# synapse.net
KiCad netlist of a schematic drawn in EAGLE
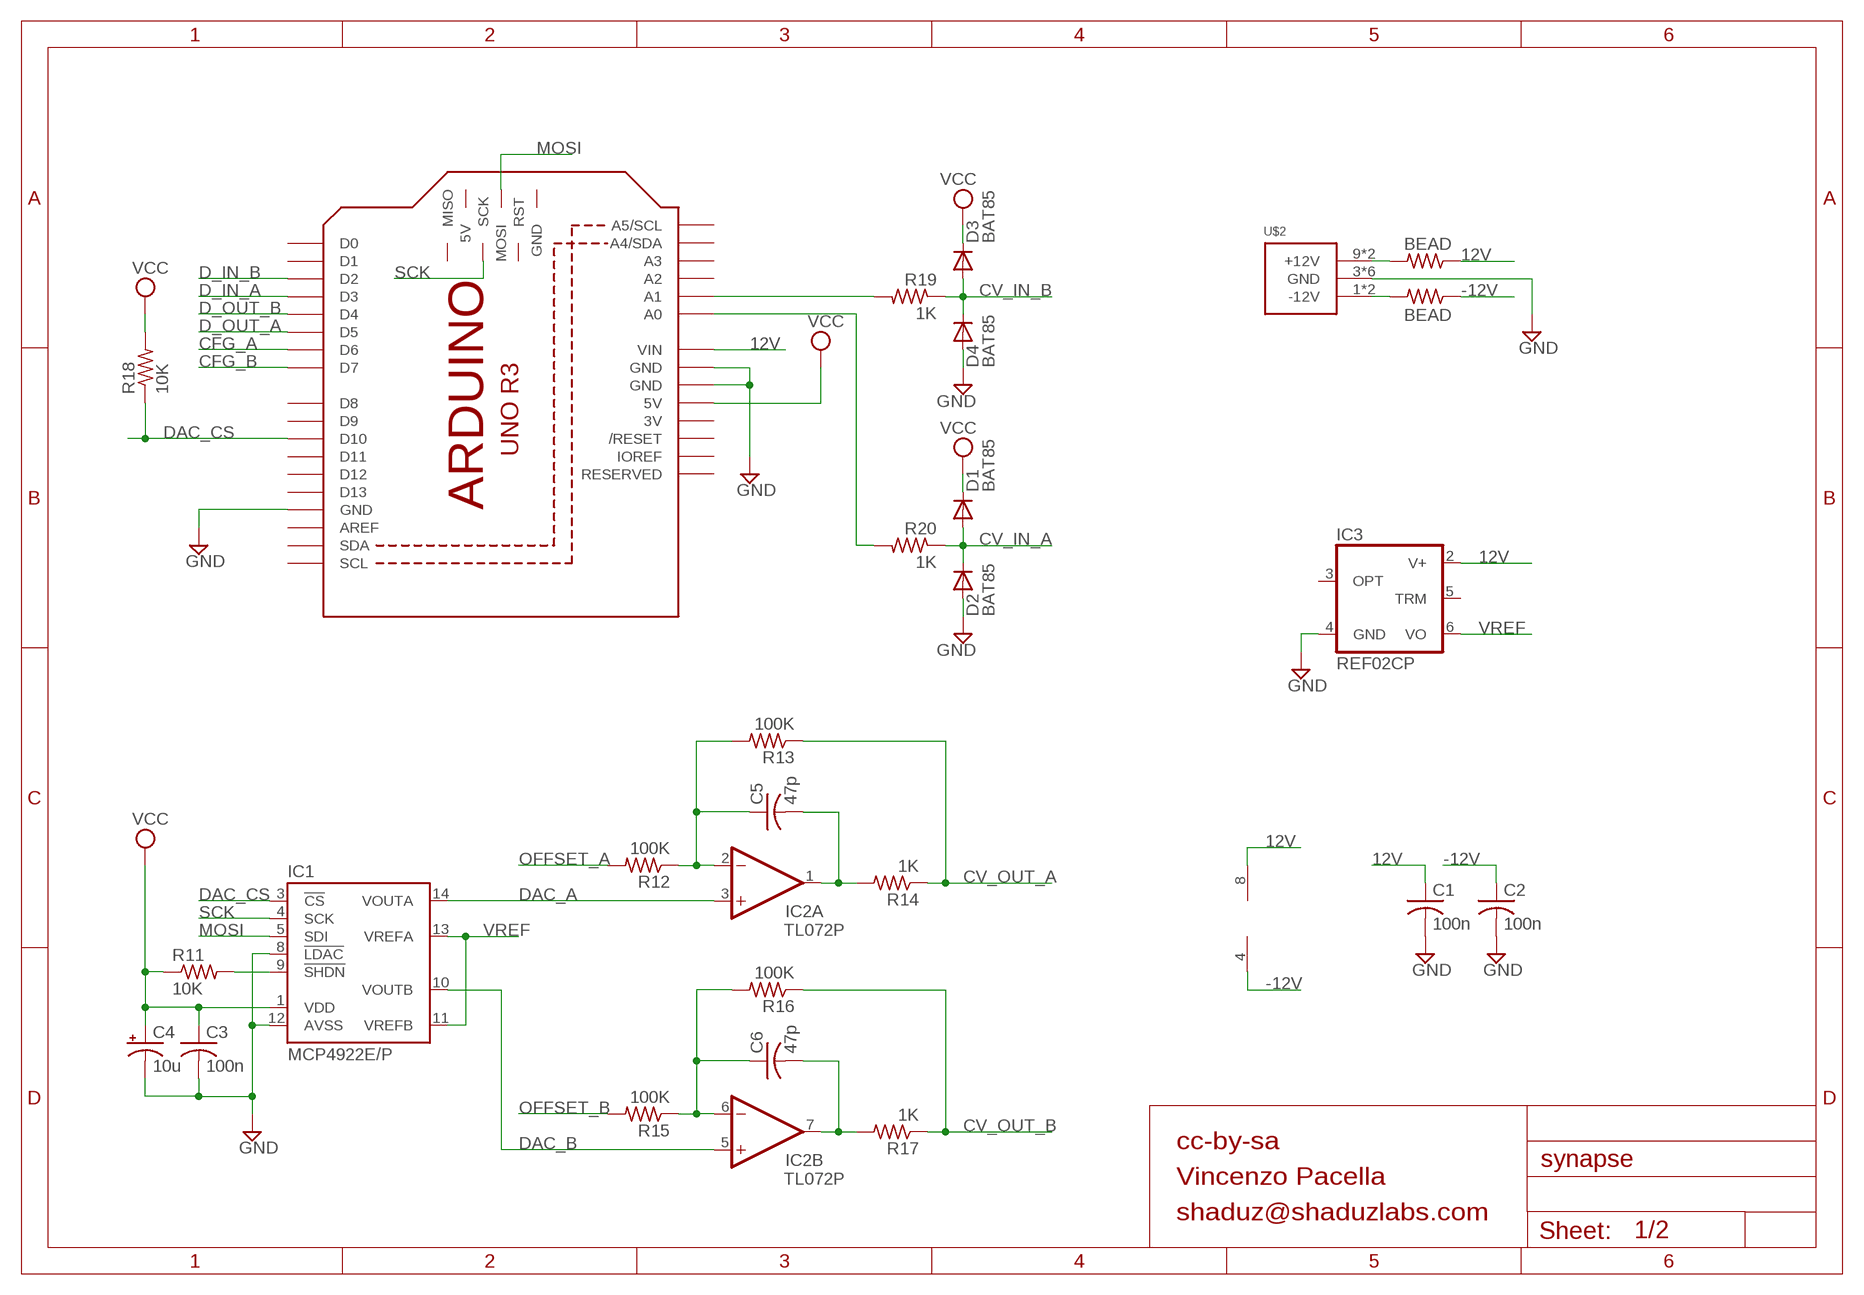
[diagram p0: schematic, sheet 1]
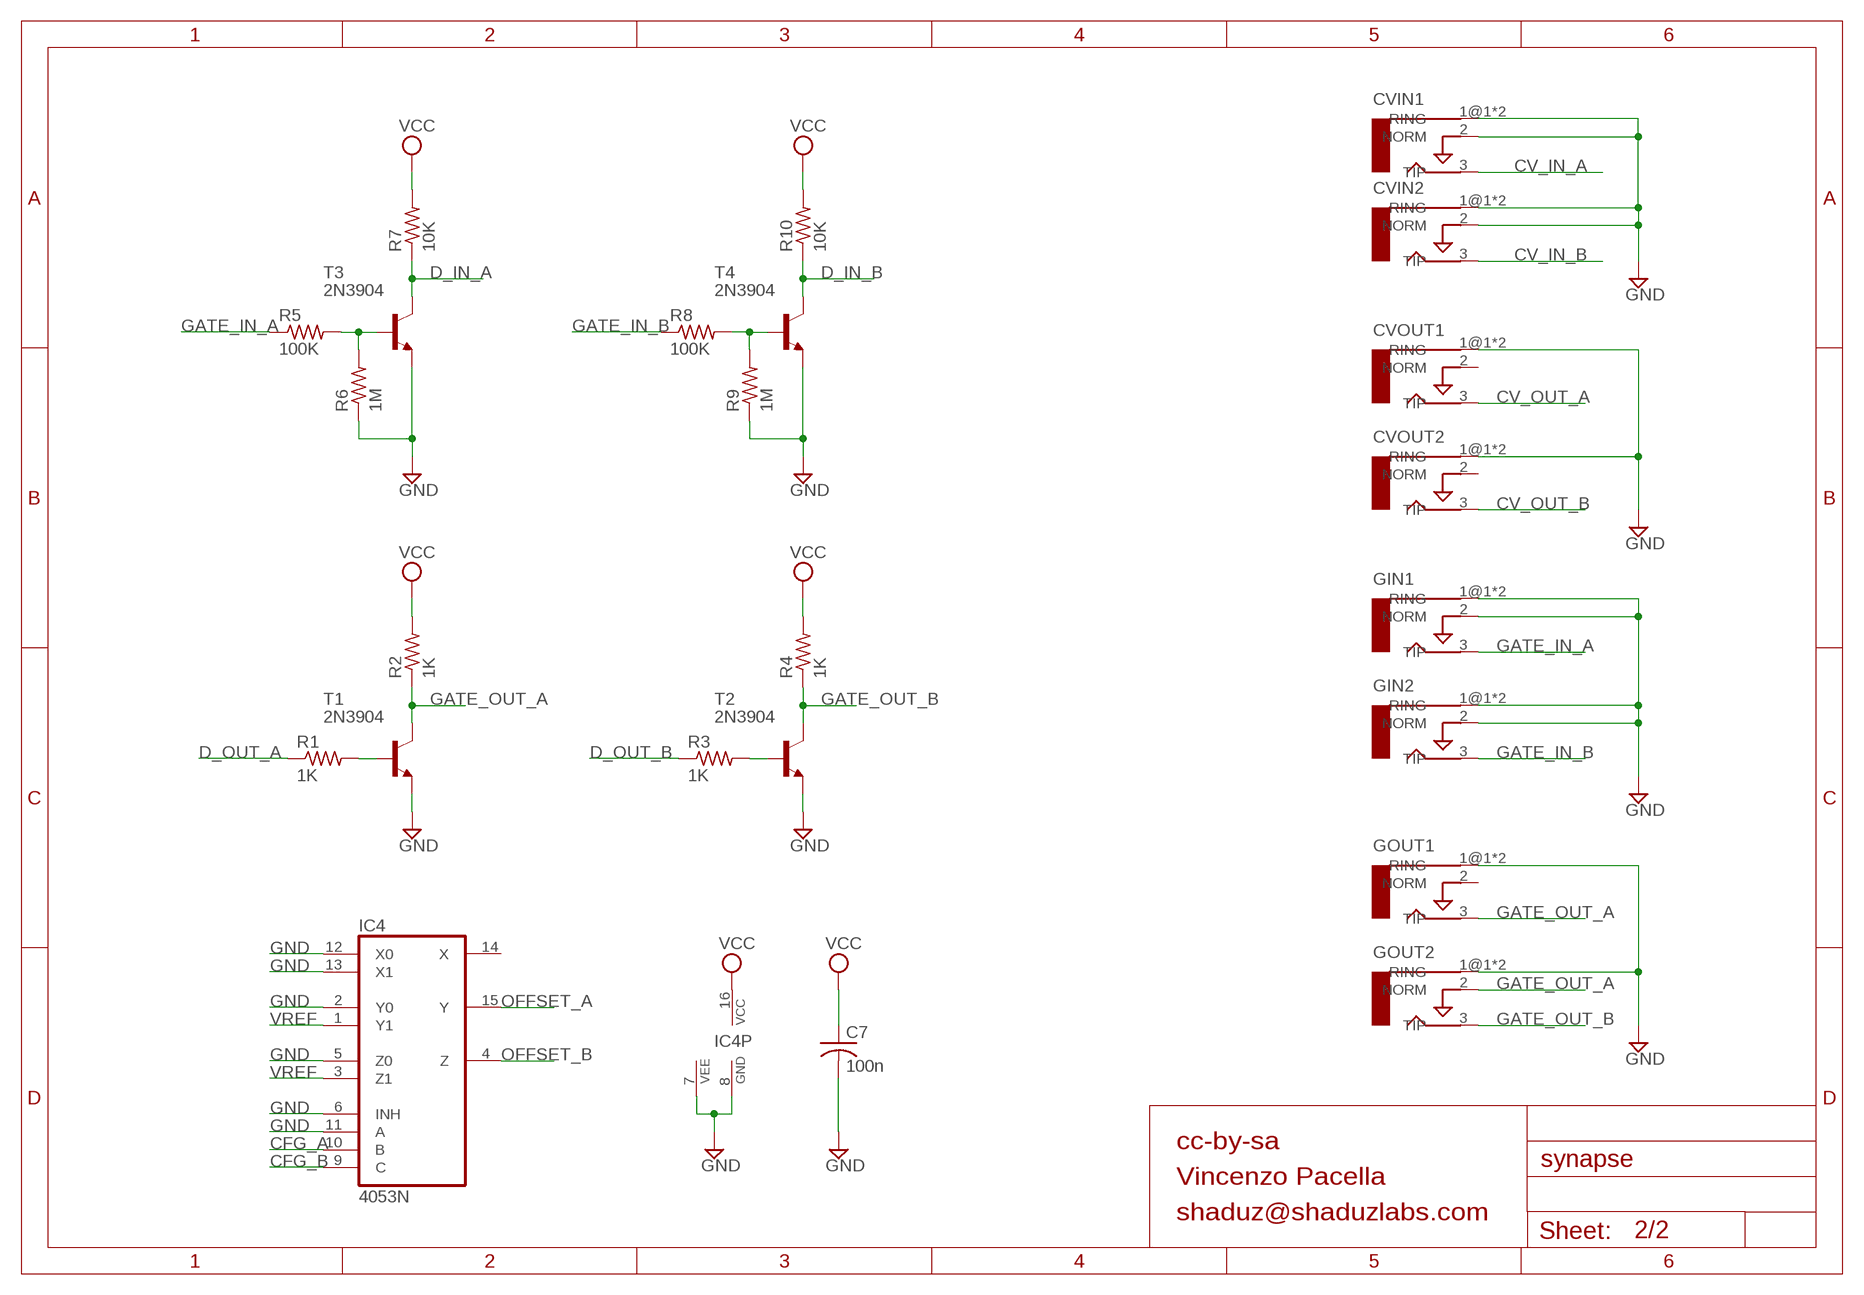
[diagram p1: schematic, sheet 2]

(export (version "E")
  (design (tool "Eeschema 10.0.6"))
  (components
    (comp (ref "C1")
      (value "100n")
      (footprint "eagle-import:C025-025X050")
      (libsource (lib "eagle-import") (part "C-US025-025X050"))
    )
    (comp (ref "C2")
      (value "100n")
      (footprint "eagle-import:C025-025X050")
      (libsource (lib "eagle-import") (part "C-US025-025X050"))
    )
    (comp (ref "C3")
      (value "100n")
      (footprint "eagle-import:C025-025X050")
      (libsource (lib "eagle-import") (part "C-US025-025X050"))
    )
    (comp (ref "C4")
      (value "10u")
      (footprint "eagle-import:E2-5")
      (libsource (lib "eagle-import") (part "CPOL-USE2-5"))
    )
    (comp (ref "C5")
      (value "47p")
      (footprint "eagle-import:C025-025X050")
      (libsource (lib "eagle-import") (part "C-US025-025X050"))
    )
    (comp (ref "C6")
      (value "47p")
      (footprint "eagle-import:C025-025X050")
      (libsource (lib "eagle-import") (part "C-US025-025X050"))
    )
    (comp (ref "D1")
      (value "BAT85")
      (footprint "eagle-import:D-5")
      (libsource (lib "eagle-import") (part "DIODE-D-5"))
    )
    (comp (ref "D2")
      (value "BAT85")
      (footprint "eagle-import:D-5")
      (libsource (lib "eagle-import") (part "DIODE-D-5"))
    )
    (comp (ref "D3")
      (value "BAT85")
      (footprint "eagle-import:D-5")
      (libsource (lib "eagle-import") (part "DIODE-D-5"))
    )
    (comp (ref "D4")
      (value "BAT85")
      (footprint "eagle-import:D-5")
      (libsource (lib "eagle-import") (part "DIODE-D-5"))
    )
    (comp (ref "IC1")
      (value "MCP4922E/P")
      (footprint "eagle-import:DIL14")
      (libsource (lib "eagle-import") (part "MCP4922E/P"))
    )
    (comp (ref "IC2")
      (value "TL072P")
      (footprint "eagle-import:DIL08")
      (libsource (lib "eagle-import") (part "TL072P"))
    )
    (comp (ref "IC3")
      (value "REF02CP")
      (footprint "eagle-import:DIL08")
      (libsource (lib "eagle-import") (part "REF02Z"))
    )
    (comp (ref "M1")
      (value "ARDUINO_R3_ICSP")
      (footprint "eagle-import:ARDUINOR3_ICSP")
      (libsource (lib "eagle-import") (part "ARDUINO_R3_ICSP"))
    )
    (comp (ref "R11")
      (value "10K")
      (footprint "eagle-import:0204_7")
      (libsource (lib "eagle-import") (part "R-US_0204/7"))
    )
    (comp (ref "R12")
      (value "100K")
      (footprint "eagle-import:0204_7")
      (libsource (lib "eagle-import") (part "R-US_0204/7"))
    )
    (comp (ref "R13")
      (value "100K")
      (footprint "eagle-import:0204_7")
      (libsource (lib "eagle-import") (part "R-US_0204/7"))
    )
    (comp (ref "R14")
      (value "1K")
      (footprint "eagle-import:0204_7")
      (libsource (lib "eagle-import") (part "R-US_0204/7"))
    )
    (comp (ref "R15")
      (value "100K")
      (footprint "eagle-import:0204_7")
      (libsource (lib "eagle-import") (part "R-US_0204/7"))
    )
    (comp (ref "R16")
      (value "100K")
      (footprint "eagle-import:0204_7")
      (libsource (lib "eagle-import") (part "R-US_0204/7"))
    )
    (comp (ref "R17")
      (value "1K")
      (footprint "eagle-import:0204_7")
      (libsource (lib "eagle-import") (part "R-US_0204/7"))
    )
    (comp (ref "R18")
      (value "10K")
      (footprint "eagle-import:0204_7")
      (libsource (lib "eagle-import") (part "R-US_0204/7"))
    )
    (comp (ref "R19")
      (value "1K")
      (footprint "eagle-import:0204_7")
      (libsource (lib "eagle-import") (part "R-US_0204/7"))
    )
    (comp (ref "R20")
      (value "1K")
      (footprint "eagle-import:0204_7")
      (libsource (lib "eagle-import") (part "R-US_0204/7"))
    )
    (comp (ref "R21")
      (value "BEAD")
      (footprint "eagle-import:0204_7")
      (libsource (lib "eagle-import") (part "R-US_0204/7"))
    )
    (comp (ref "R24")
      (value "BEAD")
      (footprint "eagle-import:0204_7")
      (libsource (lib "eagle-import") (part "R-US_0204/7"))
    )
    (comp (ref "U$2")
      (value "POWER_SIMPLE10")
      (footprint "eagle-import:POWER_10")
      (libsource (lib "eagle-import") (part "POWER_SIMPLE10"))
    )
    (comp (ref "C7")
      (value "100n")
      (footprint "eagle-import:C025-025X050")
      (libsource (lib "eagle-import") (part "C-US025-025X050"))
    )
    (comp (ref "CVIN1")
      (value "AUDIO-JACKERTHENVAR")
      (footprint "eagle-import:ERTHENVAR-JACK")
      (libsource (lib "eagle-import") (part "AUDIO-JACKERTHENVAR"))
    )
    (comp (ref "CVIN2")
      (value "AUDIO-JACKERTHENVAR")
      (footprint "eagle-import:ERTHENVAR-JACK")
      (libsource (lib "eagle-import") (part "AUDIO-JACKERTHENVAR"))
    )
    (comp (ref "CVOUT1")
      (value "AUDIO-JACKERTHENVAR")
      (footprint "eagle-import:ERTHENVAR-JACK")
      (libsource (lib "eagle-import") (part "AUDIO-JACKERTHENVAR"))
    )
    (comp (ref "CVOUT2")
      (value "AUDIO-JACKERTHENVAR")
      (footprint "eagle-import:ERTHENVAR-JACK")
      (libsource (lib "eagle-import") (part "AUDIO-JACKERTHENVAR"))
    )
    (comp (ref "GIN1")
      (value "AUDIO-JACKERTHENVAR")
      (footprint "eagle-import:ERTHENVAR-JACK")
      (libsource (lib "eagle-import") (part "AUDIO-JACKERTHENVAR"))
    )
    (comp (ref "GIN2")
      (value "AUDIO-JACKERTHENVAR")
      (footprint "eagle-import:ERTHENVAR-JACK")
      (libsource (lib "eagle-import") (part "AUDIO-JACKERTHENVAR"))
    )
    (comp (ref "GOUT1")
      (value "AUDIO-JACKERTHENVAR")
      (footprint "eagle-import:ERTHENVAR-JACK")
      (libsource (lib "eagle-import") (part "AUDIO-JACKERTHENVAR"))
    )
    (comp (ref "GOUT2")
      (value "AUDIO-JACKERTHENVAR")
      (footprint "eagle-import:ERTHENVAR-JACK")
      (libsource (lib "eagle-import") (part "AUDIO-JACKERTHENVAR"))
    )
    (comp (ref "IC4")
      (value "4053N")
      (footprint "eagle-import:DIL16")
      (libsource (lib "eagle-import") (part "4053N"))
    )
    (comp (ref "R1")
      (value "1K")
      (footprint "eagle-import:0204_7")
      (libsource (lib "eagle-import") (part "R-US_0204/7"))
    )
    (comp (ref "R2")
      (value "1K")
      (footprint "eagle-import:0204_7")
      (libsource (lib "eagle-import") (part "R-US_0204/7"))
    )
    (comp (ref "R3")
      (value "1K")
      (footprint "eagle-import:0204_7")
      (libsource (lib "eagle-import") (part "R-US_0204/7"))
    )
    (comp (ref "R4")
      (value "1K")
      (footprint "eagle-import:0204_7")
      (libsource (lib "eagle-import") (part "R-US_0204/7"))
    )
    (comp (ref "R5")
      (value "100K")
      (footprint "eagle-import:0204_7")
      (libsource (lib "eagle-import") (part "R-US_0204/7"))
    )
    (comp (ref "R6")
      (value "1M")
      (footprint "eagle-import:0204_7")
      (libsource (lib "eagle-import") (part "R-US_0204/7"))
    )
    (comp (ref "R7")
      (value "10K")
      (footprint "eagle-import:0204_7")
      (libsource (lib "eagle-import") (part "R-US_0204/7"))
    )
    (comp (ref "R8")
      (value "100K")
      (footprint "eagle-import:0204_7")
      (libsource (lib "eagle-import") (part "R-US_0204/7"))
    )
    (comp (ref "R9")
      (value "1M")
      (footprint "eagle-import:0204_7")
      (libsource (lib "eagle-import") (part "R-US_0204/7"))
    )
    (comp (ref "R10")
      (value "10K")
      (footprint "eagle-import:0204_7")
      (libsource (lib "eagle-import") (part "R-US_0204/7"))
    )
    (comp (ref "T1")
      (value "2N3904")
      (footprint "eagle-import:TO92-EBC")
      (libsource (lib "eagle-import") (part "-NPN-TO92-EBC2N3904"))
    )
    (comp (ref "T2")
      (value "2N3904")
      (footprint "eagle-import:TO92-EBC")
      (libsource (lib "eagle-import") (part "-NPN-TO92-EBC2N3904"))
    )
    (comp (ref "T3")
      (value "2N3904")
      (footprint "eagle-import:TO92-EBC")
      (libsource (lib "eagle-import") (part "-NPN-TO92-EBC2N3904"))
    )
    (comp (ref "T4")
      (value "2N3904")
      (footprint "eagle-import:TO92-EBC")
      (libsource (lib "eagle-import") (part "-NPN-TO92-EBC2N3904"))
    )
  )
  (nets
    (net (code "1") (name "-12V") (class "Default")
      (node (ref "C2") (pin "1") (pinfunction "1_1") (pintype "passive"))
      (node (ref "IC2") (pin "4") (pinfunction "V-_4") (pintype "power_in"))
      (node (ref "R24") (pin "1") (pinfunction "1_1") (pintype "passive"))
    )
    (net (code "2") (name "3V") (class "Default")
      (node (ref "M1") (pin "3V") (pinfunction "3V_3V") (pintype "power_in"))
    )
    (net (code "3") (name "12V") (class "Default")
      (node (ref "C1") (pin "1") (pinfunction "1_1") (pintype "passive"))
      (node (ref "IC2") (pin "8") (pinfunction "V+_8") (pintype "power_in"))
      (node (ref "IC3") (pin "2") (pinfunction "V+_2") (pintype "power_in"))
      (node (ref "M1") (pin "VIN") (pinfunction "VIN_VIN") (pintype "power_in"))
      (node (ref "R21") (pin "1") (pinfunction "1_1") (pintype "passive"))
    )
    (net (code "4") (name "CFG_A") (class "Default")
      (node (ref "IC4") (pin "10") (pinfunction "B_10") (pintype "input"))
      (node (ref "M1") (pin "D6") (pinfunction "D6_D6") (pintype "bidirectional"))
    )
    (net (code "5") (name "CFG_B") (class "Default")
      (node (ref "IC4") (pin "9") (pinfunction "C_9") (pintype "input"))
      (node (ref "M1") (pin "D7") (pinfunction "D7_D7") (pintype "bidirectional"))
    )
    (net (code "6") (name "CV_IN_A") (class "Default")
      (node (ref "CVIN1") (pin "3") (pinfunction "TIP_3") (pintype "bidirectional"))
      (node (ref "D1") (pin "A") (pinfunction "A_A") (pintype "passive"))
      (node (ref "D2") (pin "C") (pinfunction "C_C") (pintype "passive"))
      (node (ref "R20") (pin "1") (pinfunction "1_1") (pintype "passive"))
    )
    (net (code "7") (name "CV_IN_B") (class "Default")
      (node (ref "CVIN2") (pin "3") (pinfunction "TIP_3") (pintype "bidirectional"))
      (node (ref "D3") (pin "A") (pinfunction "A_A") (pintype "passive"))
      (node (ref "D4") (pin "C") (pinfunction "C_C") (pintype "passive"))
      (node (ref "R19") (pin "1") (pinfunction "1_1") (pintype "passive"))
    )
    (net (code "8") (name "CV_OUT_A") (class "Default")
      (node (ref "CVOUT1") (pin "3") (pinfunction "TIP_3") (pintype "bidirectional"))
      (node (ref "R13") (pin "1") (pinfunction "1_1") (pintype "passive"))
      (node (ref "R14") (pin "1") (pinfunction "1_1") (pintype "passive"))
    )
    (net (code "9") (name "CV_OUT_B") (class "Default")
      (node (ref "CVOUT2") (pin "3") (pinfunction "TIP_3") (pintype "bidirectional"))
      (node (ref "R16") (pin "1") (pinfunction "1_1") (pintype "passive"))
      (node (ref "R17") (pin "1") (pinfunction "1_1") (pintype "passive"))
    )
    (net (code "10") (name "DAC_A") (class "Default")
      (node (ref "IC1") (pin "14") (pinfunction "VOUTA_14") (pintype "output"))
      (node (ref "IC2") (pin "3") (pinfunction "+IN_3") (pintype "input"))
    )
    (net (code "11") (name "DAC_B") (class "Default")
      (node (ref "IC1") (pin "10") (pinfunction "VOUTB_10") (pintype "output"))
      (node (ref "IC2") (pin "5") (pinfunction "+IN_5") (pintype "input"))
    )
    (net (code "12") (name "DAC_CS") (class "Default")
      (node (ref "IC1") (pin "3") (pinfunction "~{CS}_3") (pintype "input"))
      (node (ref "M1") (pin "D10") (pinfunction "D10_D10") (pintype "bidirectional"))
      (node (ref "R18") (pin "1") (pinfunction "1_1") (pintype "passive"))
    )
    (net (code "13") (name "D_IN_A") (class "Default")
      (node (ref "M1") (pin "D3") (pinfunction "D3_D3") (pintype "bidirectional"))
      (node (ref "R7") (pin "1") (pinfunction "1_1") (pintype "passive"))
      (node (ref "T3") (pin "C") (pinfunction "C_C") (pintype "passive"))
    )
    (net (code "14") (name "D_IN_B") (class "Default")
      (node (ref "M1") (pin "D2") (pinfunction "D2_D2") (pintype "bidirectional"))
      (node (ref "R10") (pin "1") (pinfunction "1_1") (pintype "passive"))
      (node (ref "T4") (pin "C") (pinfunction "C_C") (pintype "passive"))
    )
    (net (code "15") (name "D_OUT_A") (class "Default")
      (node (ref "M1") (pin "D5") (pinfunction "D5_D5") (pintype "bidirectional"))
      (node (ref "R1") (pin "1") (pinfunction "1_1") (pintype "passive"))
    )
    (net (code "16") (name "D_OUT_B") (class "Default")
      (node (ref "M1") (pin "D4") (pinfunction "D4_D4") (pintype "bidirectional"))
      (node (ref "R3") (pin "1") (pinfunction "1_1") (pintype "passive"))
    )
    (net (code "17") (name "GATE_IN_A") (class "Default")
      (node (ref "GIN1") (pin "3") (pinfunction "TIP_3") (pintype "bidirectional"))
      (node (ref "R5") (pin "1") (pinfunction "1_1") (pintype "passive"))
    )
    (net (code "18") (name "GATE_IN_B") (class "Default")
      (node (ref "GIN2") (pin "3") (pinfunction "TIP_3") (pintype "bidirectional"))
      (node (ref "R8") (pin "1") (pinfunction "1_1") (pintype "passive"))
    )
    (net (code "19") (name "GATE_OUT_A") (class "Default")
      (node (ref "GOUT1") (pin "3") (pinfunction "TIP_3") (pintype "bidirectional"))
      (node (ref "GOUT2") (pin "2") (pinfunction "NORM_2") (pintype "bidirectional"))
      (node (ref "R2") (pin "1") (pinfunction "1_1") (pintype "passive"))
      (node (ref "T1") (pin "C") (pinfunction "C_C") (pintype "passive"))
    )
    (net (code "20") (name "GATE_OUT_B") (class "Default")
      (node (ref "GOUT2") (pin "3") (pinfunction "TIP_3") (pintype "bidirectional"))
      (node (ref "R4") (pin "1") (pinfunction "1_1") (pintype "passive"))
      (node (ref "T2") (pin "C") (pinfunction "C_C") (pintype "passive"))
    )
    (net (code "21") (name "GND") (class "Default")
      (node (ref "C1") (pin "2") (pinfunction "2_2") (pintype "passive"))
      (node (ref "C2") (pin "2") (pinfunction "2_2") (pintype "passive"))
      (node (ref "C3") (pin "2") (pinfunction "2_2") (pintype "passive"))
      (node (ref "C4") (pin "-") (pinfunction "-_-") (pintype "passive"))
      (node (ref "C7") (pin "2") (pinfunction "2_2") (pintype "passive"))
      (node (ref "CVIN1") (pin "1@1") (pinfunction "RING_1@1") (pintype "bidirectional"))
      (node (ref "CVIN1") (pin "1@2") (pinfunction "RING_1@2") (pintype "bidirectional"))
      (node (ref "CVIN1") (pin "2") (pinfunction "NORM_2") (pintype "bidirectional"))
      (node (ref "CVIN2") (pin "1@1") (pinfunction "RING_1@1") (pintype "bidirectional"))
      (node (ref "CVIN2") (pin "1@2") (pinfunction "RING_1@2") (pintype "bidirectional"))
      (node (ref "CVIN2") (pin "2") (pinfunction "NORM_2") (pintype "bidirectional"))
      (node (ref "CVOUT1") (pin "1@1") (pinfunction "RING_1@1") (pintype "bidirectional"))
      (node (ref "CVOUT1") (pin "1@2") (pinfunction "RING_1@2") (pintype "bidirectional"))
      (node (ref "CVOUT2") (pin "1@1") (pinfunction "RING_1@1") (pintype "bidirectional"))
      (node (ref "CVOUT2") (pin "1@2") (pinfunction "RING_1@2") (pintype "bidirectional"))
      (node (ref "D2") (pin "A") (pinfunction "A_A") (pintype "passive"))
      (node (ref "D4") (pin "A") (pinfunction "A_A") (pintype "passive"))
      (node (ref "GIN1") (pin "1@1") (pinfunction "RING_1@1") (pintype "bidirectional"))
      (node (ref "GIN1") (pin "1@2") (pinfunction "RING_1@2") (pintype "bidirectional"))
      (node (ref "GIN1") (pin "2") (pinfunction "NORM_2") (pintype "bidirectional"))
      (node (ref "GIN2") (pin "1@1") (pinfunction "RING_1@1") (pintype "bidirectional"))
      (node (ref "GIN2") (pin "1@2") (pinfunction "RING_1@2") (pintype "bidirectional"))
      (node (ref "GIN2") (pin "2") (pinfunction "NORM_2") (pintype "bidirectional"))
      (node (ref "GOUT1") (pin "1@1") (pinfunction "RING_1@1") (pintype "bidirectional"))
      (node (ref "GOUT1") (pin "1@2") (pinfunction "RING_1@2") (pintype "bidirectional"))
      (node (ref "GOUT2") (pin "1@1") (pinfunction "RING_1@1") (pintype "bidirectional"))
      (node (ref "GOUT2") (pin "1@2") (pinfunction "RING_1@2") (pintype "bidirectional"))
      (node (ref "IC1") (pin "12") (pinfunction "AVSS_12") (pintype "power_in"))
      (node (ref "IC1") (pin "8") (pinfunction "~{LDAC}_8") (pintype "input"))
      (node (ref "IC3") (pin "4") (pinfunction "GND_4") (pintype "power_in"))
      (node (ref "IC4") (pin "11") (pinfunction "A_11") (pintype "input"))
      (node (ref "IC4") (pin "12") (pinfunction "X0_12") (pintype "bidirectional"))
      (node (ref "IC4") (pin "13") (pinfunction "X1_13") (pintype "bidirectional"))
      (node (ref "IC4") (pin "2") (pinfunction "Y0_2") (pintype "bidirectional"))
      (node (ref "IC4") (pin "5") (pinfunction "Z0_5") (pintype "bidirectional"))
      (node (ref "IC4") (pin "6") (pinfunction "INH_6") (pintype "input"))
      (node (ref "IC4") (pin "7") (pinfunction "VEE_7") (pintype "power_in"))
      (node (ref "IC4") (pin "8") (pinfunction "GND_8") (pintype "power_in"))
      (node (ref "M1") (pin "GND") (pinfunction "GND_GND") (pintype "power_in"))
      (node (ref "M1") (pin "GND@1") (pinfunction "GND_GND@1") (pintype "power_in"))
      (node (ref "M1") (pin "GND@3") (pinfunction "GND_GND@3") (pintype "power_in"))
      (node (ref "R6") (pin "1") (pinfunction "1_1") (pintype "passive"))
      (node (ref "R9") (pin "1") (pinfunction "1_1") (pintype "passive"))
      (node (ref "T1") (pin "E") (pinfunction "E_E") (pintype "passive"))
      (node (ref "T2") (pin "E") (pinfunction "E_E") (pintype "passive"))
      (node (ref "T3") (pin "E") (pinfunction "E_E") (pintype "passive"))
      (node (ref "T4") (pin "E") (pinfunction "E_E") (pintype "passive"))
      (node (ref "U$2") (pin "3") (pinfunction "GND_3") (pintype "bidirectional"))
      (node (ref "U$2") (pin "4") (pinfunction "GND_4") (pintype "bidirectional"))
      (node (ref "U$2") (pin "5") (pinfunction "GND_5") (pintype "bidirectional"))
      (node (ref "U$2") (pin "6") (pinfunction "GND_6") (pintype "bidirectional"))
      (node (ref "U$2") (pin "7") (pinfunction "GND_7") (pintype "bidirectional"))
      (node (ref "U$2") (pin "8") (pinfunction "GND_8") (pintype "bidirectional"))
    )
    (net (code "22") (name "MOSI") (class "Default")
      (node (ref "IC1") (pin "5") (pinfunction "SDI_5") (pintype "input"))
      (node (ref "M1") (pin "MOSI") (pinfunction "MOSI_MOSI") (pintype "passive"))
    )
    (net (code "23") (name "Net-(IC1-~{SHDN})") (class "Default")
      (node (ref "IC1") (pin "9") (pinfunction "~{SHDN}_9") (pintype "input"))
      (node (ref "R11") (pin "2") (pinfunction "2_2") (pintype "passive"))
    )
    (net (code "24") (name "Net-(IC2A--IN)") (class "Default")
      (node (ref "C5") (pin "1") (pinfunction "1_1") (pintype "passive"))
      (node (ref "IC2") (pin "2") (pinfunction "-IN_2") (pintype "input"))
      (node (ref "R12") (pin "1") (pinfunction "1_1") (pintype "passive"))
      (node (ref "R13") (pin "2") (pinfunction "2_2") (pintype "passive"))
    )
    (net (code "25") (name "Net-(IC2A-OUT)") (class "Default")
      (node (ref "C5") (pin "2") (pinfunction "2_2") (pintype "passive"))
      (node (ref "IC2") (pin "1") (pinfunction "OUT_1") (pintype "output"))
      (node (ref "R14") (pin "2") (pinfunction "2_2") (pintype "passive"))
    )
    (net (code "26") (name "Net-(IC2B--IN)") (class "Default")
      (node (ref "C6") (pin "1") (pinfunction "1_1") (pintype "passive"))
      (node (ref "IC2") (pin "6") (pinfunction "-IN_6") (pintype "input"))
      (node (ref "R15") (pin "1") (pinfunction "1_1") (pintype "passive"))
      (node (ref "R16") (pin "2") (pinfunction "2_2") (pintype "passive"))
    )
    (net (code "27") (name "Net-(IC2B-OUT)") (class "Default")
      (node (ref "C6") (pin "2") (pinfunction "2_2") (pintype "passive"))
      (node (ref "IC2") (pin "7") (pinfunction "OUT_7") (pintype "output"))
      (node (ref "R17") (pin "2") (pinfunction "2_2") (pintype "passive"))
    )
    (net (code "28") (name "Net-(M1-PadA0)") (class "Default")
      (node (ref "M1") (pin "A0") (pinfunction "A0_A0") (pintype "bidirectional"))
      (node (ref "R20") (pin "2") (pinfunction "2_2") (pintype "passive"))
    )
    (net (code "29") (name "Net-(M1-PadA1)") (class "Default")
      (node (ref "M1") (pin "A1") (pinfunction "A1_A1") (pintype "bidirectional"))
      (node (ref "R19") (pin "2") (pinfunction "2_2") (pintype "passive"))
    )
    (net (code "30") (name "Net-(R1-Pad2)") (class "Default")
      (node (ref "R1") (pin "2") (pinfunction "2_2") (pintype "passive"))
      (node (ref "T1") (pin "B") (pinfunction "B_B") (pintype "passive"))
    )
    (net (code "31") (name "Net-(R3-Pad2)") (class "Default")
      (node (ref "R3") (pin "2") (pinfunction "2_2") (pintype "passive"))
      (node (ref "T2") (pin "B") (pinfunction "B_B") (pintype "passive"))
    )
    (net (code "32") (name "Net-(R5-Pad2)") (class "Default")
      (node (ref "R5") (pin "2") (pinfunction "2_2") (pintype "passive"))
      (node (ref "R6") (pin "2") (pinfunction "2_2") (pintype "passive"))
      (node (ref "T3") (pin "B") (pinfunction "B_B") (pintype "passive"))
    )
    (net (code "33") (name "Net-(R8-Pad2)") (class "Default")
      (node (ref "R8") (pin "2") (pinfunction "2_2") (pintype "passive"))
      (node (ref "R9") (pin "2") (pinfunction "2_2") (pintype "passive"))
      (node (ref "T4") (pin "B") (pinfunction "B_B") (pintype "passive"))
    )
    (net (code "34") (name "Net-(R21-Pad2)") (class "Default")
      (node (ref "R21") (pin "2") (pinfunction "2_2") (pintype "passive"))
      (node (ref "U$2") (pin "10") (pinfunction "+12V_10") (pintype "bidirectional"))
      (node (ref "U$2") (pin "9") (pinfunction "+12V_9") (pintype "bidirectional"))
    )
    (net (code "35") (name "Net-(R24-Pad2)") (class "Default")
      (node (ref "R24") (pin "2") (pinfunction "2_2") (pintype "passive"))
      (node (ref "U$2") (pin "1") (pinfunction "-12V_1") (pintype "bidirectional"))
      (node (ref "U$2") (pin "2") (pinfunction "-12V_2") (pintype "bidirectional"))
    )
    (net (code "36") (name "OFFSET_A") (class "Default")
      (node (ref "IC4") (pin "15") (pinfunction "Y_15") (pintype "bidirectional"))
      (node (ref "R12") (pin "2") (pinfunction "2_2") (pintype "passive"))
    )
    (net (code "37") (name "OFFSET_B") (class "Default")
      (node (ref "IC4") (pin "4") (pinfunction "Z_4") (pintype "bidirectional"))
      (node (ref "R15") (pin "2") (pinfunction "2_2") (pintype "passive"))
    )
    (net (code "38") (name "SCK") (class "Default")
      (node (ref "IC1") (pin "4") (pinfunction "SCK_4") (pintype "input"))
      (node (ref "M1") (pin "SCK") (pinfunction "SCK_SCK") (pintype "passive"))
    )
    (net (code "39") (name "VCC") (class "Default")
      (node (ref "C3") (pin "1") (pinfunction "1_1") (pintype "passive"))
      (node (ref "C4") (pin "+") (pinfunction "+_+") (pintype "passive"))
      (node (ref "C7") (pin "1") (pinfunction "1_1") (pintype "passive"))
      (node (ref "D1") (pin "C") (pinfunction "C_C") (pintype "passive"))
      (node (ref "D3") (pin "C") (pinfunction "C_C") (pintype "passive"))
      (node (ref "IC1") (pin "1") (pinfunction "VDD_1") (pintype "power_in"))
      (node (ref "IC4") (pin "16") (pinfunction "VCC_16") (pintype "power_in"))
      (node (ref "M1") (pin "5V") (pinfunction "5V_5V") (pintype "power_in"))
      (node (ref "R10") (pin "2") (pinfunction "2_2") (pintype "passive"))
      (node (ref "R11") (pin "1") (pinfunction "1_1") (pintype "passive"))
      (node (ref "R18") (pin "2") (pinfunction "2_2") (pintype "passive"))
      (node (ref "R2") (pin "2") (pinfunction "2_2") (pintype "passive"))
      (node (ref "R4") (pin "2") (pinfunction "2_2") (pintype "passive"))
      (node (ref "R7") (pin "2") (pinfunction "2_2") (pintype "passive"))
    )
    (net (code "40") (name "VREF") (class "Default")
      (node (ref "IC1") (pin "11") (pinfunction "VREFB_11") (pintype "input"))
      (node (ref "IC1") (pin "13") (pinfunction "VREFA_13") (pintype "input"))
      (node (ref "IC3") (pin "6") (pinfunction "VO_6") (pintype "output"))
      (node (ref "IC4") (pin "1") (pinfunction "Y1_1") (pintype "bidirectional"))
      (node (ref "IC4") (pin "3") (pinfunction "Z1_3") (pintype "bidirectional"))
    )
    (net (code "41") (name "unconnected-(CVOUT1-NORM-Pad2)") (class "Default")
      (node (ref "CVOUT1") (pin "2") (pinfunction "NORM_2") (pintype "bidirectional"))
    )
    (net (code "42") (name "unconnected-(CVOUT2-NORM-Pad2)") (class "Default")
      (node (ref "CVOUT2") (pin "2") (pinfunction "NORM_2") (pintype "bidirectional"))
    )
    (net (code "43") (name "unconnected-(GOUT1-NORM-Pad2)") (class "Default")
      (node (ref "GOUT1") (pin "2") (pinfunction "NORM_2") (pintype "bidirectional"))
    )
    (net (code "44") (name "unconnected-(IC3-OPT-Pad3)") (class "Default")
      (node (ref "IC3") (pin "3") (pinfunction "OPT_3") (pintype "output"))
    )
    (net (code "45") (name "unconnected-(IC3-TRM-Pad5)") (class "Default")
      (node (ref "IC3") (pin "5") (pinfunction "TRM_5") (pintype "input"))
    )
    (net (code "46") (name "unconnected-(IC4A-X-Pad14)") (class "Default")
      (node (ref "IC4") (pin "14") (pinfunction "X_14") (pintype "bidirectional"))
    )
    (net (code "47") (name "unconnected-(M1-5V-Pad5V_ICSP)") (class "Default")
      (node (ref "M1") (pin "5V_ICSP") (pinfunction "5V_5V_ICSP") (pintype "passive"))
    )
    (net (code "48") (name "unconnected-(M1-A4{slash}SDA-PadA4)") (class "Default")
      (node (ref "M1") (pin "A4") (pinfunction "A4/SDA_A4") (pintype "bidirectional"))
    )
    (net (code "49") (name "unconnected-(M1-A5{slash}SCL-PadA5)") (class "Default")
      (node (ref "M1") (pin "A5") (pinfunction "A5/SCL_A5") (pintype "bidirectional"))
    )
    (net (code "50") (name "unconnected-(M1-GND-PadGND@2)") (class "Default")
      (node (ref "M1") (pin "GND@2") (pinfunction "GND_GND@2") (pintype "passive"))
    )
    (net (code "51") (name "unconnected-(M1-PadA2)") (class "Default")
      (node (ref "M1") (pin "A2") (pinfunction "A2_A2") (pintype "bidirectional"))
    )
    (net (code "52") (name "unconnected-(M1-PadA3)") (class "Default")
      (node (ref "M1") (pin "A3") (pinfunction "A3_A3") (pintype "bidirectional"))
    )
    (net (code "53") (name "unconnected-(M1-PadAREF)") (class "Default")
      (node (ref "M1") (pin "AREF") (pinfunction "AREF_AREF") (pintype "bidirectional"))
    )
    (net (code "54") (name "unconnected-(M1-PadD0)") (class "Default")
      (node (ref "M1") (pin "D0") (pinfunction "D0_D0") (pintype "bidirectional"))
    )
    (net (code "55") (name "unconnected-(M1-PadD1)") (class "Default")
      (node (ref "M1") (pin "D1") (pinfunction "D1_D1") (pintype "bidirectional"))
    )
    (net (code "56") (name "unconnected-(M1-PadD8)") (class "Default")
      (node (ref "M1") (pin "D8") (pinfunction "D8_D8") (pintype "bidirectional"))
    )
    (net (code "57") (name "unconnected-(M1-PadD9)") (class "Default")
      (node (ref "M1") (pin "D9") (pinfunction "D9_D9") (pintype "bidirectional"))
    )
    (net (code "58") (name "unconnected-(M1-PadD11)") (class "Default")
      (node (ref "M1") (pin "D11") (pinfunction "D11_D11") (pintype "bidirectional"))
    )
    (net (code "59") (name "unconnected-(M1-PadD12)") (class "Default")
      (node (ref "M1") (pin "D12") (pinfunction "D12_D12") (pintype "bidirectional"))
    )
    (net (code "60") (name "unconnected-(M1-PadD13)") (class "Default")
      (node (ref "M1") (pin "D13") (pinfunction "D13_D13") (pintype "bidirectional"))
    )
    (net (code "61") (name "unconnected-(M1-PadIOREF)") (class "Default")
      (node (ref "M1") (pin "IOREF") (pinfunction "IOREF_IOREF") (pintype "output"))
    )
    (net (code "62") (name "unconnected-(M1-PadMISO)") (class "Default")
      (node (ref "M1") (pin "MISO") (pinfunction "MISO_MISO") (pintype "passive"))
    )
    (net (code "63") (name "unconnected-(M1-PadRESERVED)") (class "Default")
      (node (ref "M1") (pin "RESERVED") (pinfunction "RESERVED_RESERVED") (pintype "no_connect"))
    )
    (net (code "64") (name "unconnected-(M1-PadSCL)") (class "Default")
      (node (ref "M1") (pin "SCL") (pinfunction "SCL_SCL") (pintype "bidirectional"))
    )
    (net (code "65") (name "unconnected-(M1-PadSDA)") (class "Default")
      (node (ref "M1") (pin "SDA") (pinfunction "SDA_SDA") (pintype "bidirectional"))
    )
    (net (code "66") (name "unconnected-(M1-RST-PadRESET_ICSP)") (class "Default")
      (node (ref "M1") (pin "RESET_ICSP") (pinfunction "RST_RESET_ICSP") (pintype "passive"))
    )
    (net (code "67") (name "unconnected-(M1-{slash}RESET-PadRESET)") (class "Default")
      (node (ref "M1") (pin "RESET") (pinfunction "/RESET_RESET") (pintype "bidirectional"))
    )
  )
)
